# DAC_ADC_External.net
KiCad netlist of a schematic drawn in Altium Designer
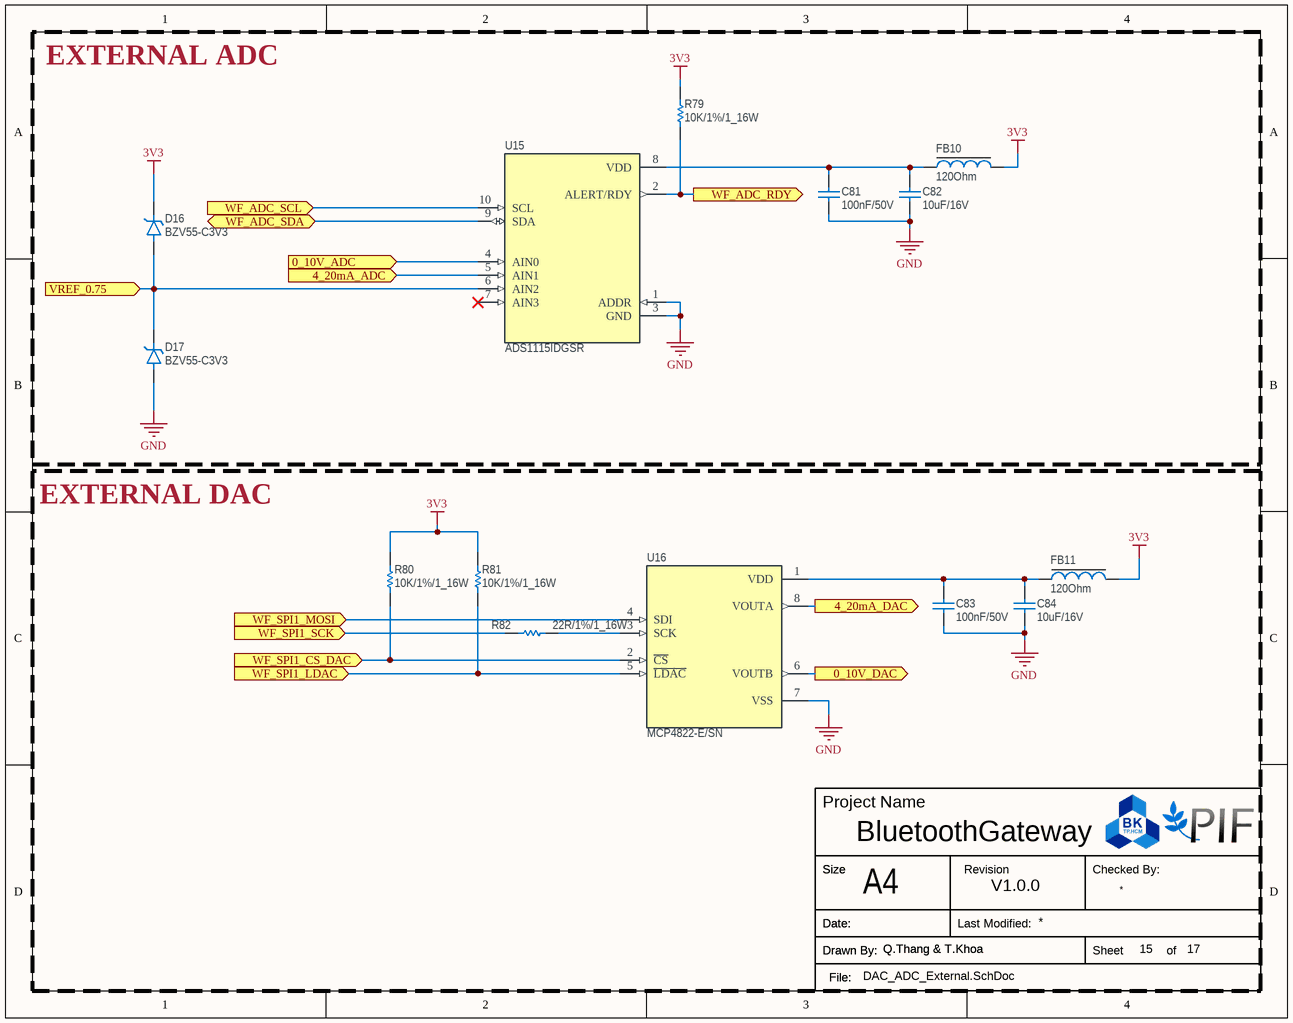
[diagram p0: DAC_ADC_External.SchDoc]

(export (version "E")
  (design (tool "Eeschema 10.0.6"))
  (components
    (comp (ref "C81")
      (value "100nF/50V")
      (footprint "CAP_0603")
      (description "CAP, size 0603, 100nF, 50V")
      (fields (field (name "SUPPLY PART NUMBER") "Tụ Gốm 0603 100nF (0.1uF) 50V"))
      (libsource (lib "BluetoothTracking") (part "Ceramic_Cap_100nF_50V_0603"))
    )
    (comp (ref "C82")
      (value "10uF/16V")
      (footprint "CAP_0603")
      (description "CAP, size 0603, 10uF, 16V")
      (fields (field (name "SUPPLY PART NUMBER") "Tụ Gốm 0603 10uF 16V"))
      (libsource (lib "BluetoothTracking") (part "Ceramic_Cap_10uF_16V_0603"))
    )
    (comp (ref "C83")
      (value "100nF/50V")
      (footprint "CAP_0603")
      (description "CAP, size 0603, 100nF, 50V")
      (fields (field (name "SUPPLY PART NUMBER") "Tụ Gốm 0603 100nF (0.1uF) 50V"))
      (libsource (lib "BluetoothTracking") (part "Ceramic_Cap_100nF_50V_0603"))
    )
    (comp (ref "C84")
      (value "10uF/16V")
      (footprint "CAP_0603")
      (description "CAP, size 0603, 10uF, 16V")
      (fields (field (name "SUPPLY PART NUMBER") "Tụ Gốm 0603 10uF 16V"))
      (libsource (lib "BluetoothTracking") (part "Ceramic_Cap_10uF_16V_0603"))
    )
    (comp (ref "D16")
      (value "BZV55-C3V3")
      (footprint "SOD-80")
      (description "DIODE ZENER 3.3V 500 mW")
      (libsource (lib "BluetoothTracking") (part "Diode_BZV55C3V3"))
    )
    (comp (ref "D17")
      (value "BZV55-C3V3")
      (footprint "SOD-80")
      (description "DIODE ZENER 3.3V 500 mW")
      (libsource (lib "BluetoothTracking") (part "Diode_BZV55C3V3"))
    )
    (comp (ref "FB10")
      (value "120Ohm")
      (footprint "Ferrite_Bead_0805")
      (description "Ferrite Bead, size 0805, 120Ohm, 2A")
      (fields (field (name "SUPPLY PART NUMBER") "CBW201209U121T Ferrite Beads 2A 120 Ohm 0805"))
      (libsource (lib "BluetoothTracking") (part "Ferrite_Bead_120Ohm_2A_0805"))
    )
    (comp (ref "FB11")
      (value "120Ohm")
      (footprint "Ferrite_Bead_0805")
      (description "Ferrite Bead, size 0805, 120Ohm, 2A")
      (fields (field (name "SUPPLY PART NUMBER") "CBW201209U121T Ferrite Beads 2A 120 Ohm 0805"))
      (libsource (lib "BluetoothTracking") (part "Ferrite_Bead_120Ohm_2A_0805"))
    )
    (comp (ref "R79")
      (value "10K/1%/1_16W")
      (footprint "RESISTOR_0402")
      (description "Resistor 0402 10KOhm 1% 1_16W")
      (fields (field (name "SUPPLY PART NUMBER") "Điện Trở 10 KOhm 0402 1%"))
      (libsource (lib "BluetoothTracking") (part "Res_10K_0402_1%"))
    )
    (comp (ref "R80")
      (value "10K/1%/1_16W")
      (footprint "RESISTOR_0402")
      (description "Resistor 0402 10KOhm 1% 1_16W")
      (fields (field (name "SUPPLY PART NUMBER") "Điện Trở 10 KOhm 0402 1%"))
      (libsource (lib "BluetoothTracking") (part "Res_10K_0402_1%"))
    )
    (comp (ref "R81")
      (value "10K/1%/1_16W")
      (footprint "RESISTOR_0402")
      (description "Resistor 0402 10KOhm 1% 1_16W")
      (fields (field (name "SUPPLY PART NUMBER") "Điện Trở 10 KOhm 0402 1%"))
      (libsource (lib "BluetoothTracking") (part "Res_10K_0402_1%"))
    )
    (comp (ref "R82")
      (value "22R/1%/1_16W")
      (footprint "RESISTOR_0402")
      (description "Resistor 0402 22 Ohm 1% 1_16W")
      (libsource (lib "BluetoothTracking") (part "Res_22R_0402_1%"))
    )
    (comp (ref "U15")
      (value "ADS1115IDGSR")
      (footprint "VSSOP-10")
      (fields (field (name "SUPPLY PART NUMBER") "ADS1115IDGSR IC ADC 16-Bit Sigma-Delta 10-VSSOP"))
      (libsource (lib "BluetoothTracking") (part "ADS1115IDGSR"))
    )
    (comp (ref "U16")
      (value "MCP4822-E/SN")
      (footprint "SOIC-8")
      (description "12 Bit Digital to Analog Converter 2 8-SOIC")
      (fields (field (name "SUPPLY PART NUMBER") "MCP4822-E/SN SOIC-8 DAC 12Bit Chính Hãng Microchip"))
      (libsource (lib "BluetoothTracking") (part "MCP4822-E/SN"))
    )
  )
  (nets
    (net (code "1") (name "/0_10V_ADC") (class "Default")
      (node (ref "U15") (pin "4") (pinfunction "AIN0_4") (pintype "input"))
    )
    (net (code "2") (name "/0_10V_DAC") (class "Default")
      (node (ref "U16") (pin "6") (pinfunction "VOUTB_6") (pintype "output"))
    )
    (net (code "3") (name "/4_20mA_ADC") (class "Default")
      (node (ref "U15") (pin "5") (pinfunction "AIN1_5") (pintype "input"))
    )
    (net (code "4") (name "/4_20mA_DAC") (class "Default")
      (node (ref "U16") (pin "8") (pinfunction "VOUTA_8") (pintype "output"))
    )
    (net (code "5") (name "/VREF_0.75") (class "Default")
      (node (ref "D16") (pin "A") (pinfunction "A_A") (pintype "passive"))
      (node (ref "D17") (pin "C") (pinfunction "C_C") (pintype "passive"))
      (node (ref "U15") (pin "6") (pinfunction "AIN2_6") (pintype "input"))
    )
    (net (code "6") (name "/WF_ADC_RDY") (class "Default")
      (node (ref "R79") (pin "1") (pinfunction "1_1") (pintype "passive"))
      (node (ref "U15") (pin "2") (pinfunction "ALERT/RDY_2") (pintype "output"))
    )
    (net (code "7") (name "/WF_ADC_SCL") (class "Default")
      (node (ref "U15") (pin "10") (pinfunction "SCL_10") (pintype "input"))
    )
    (net (code "8") (name "/WF_ADC_SDA") (class "Default")
      (node (ref "U15") (pin "9") (pinfunction "SDA_9") (pintype "bidirectional"))
    )
    (net (code "9") (name "/WF_SPI1_CS_DAC") (class "Default")
      (node (ref "R80") (pin "1") (pinfunction "1_1") (pintype "passive"))
      (node (ref "U16") (pin "2") (pinfunction "~{CS}_2") (pintype "input"))
    )
    (net (code "10") (name "/WF_SPI1_LDAC") (class "Default")
      (node (ref "R81") (pin "1") (pinfunction "1_1") (pintype "passive"))
      (node (ref "U16") (pin "5") (pinfunction "~{LDAC}_5") (pintype "input"))
    )
    (net (code "11") (name "/WF_SPI1_MOSI") (class "Default")
      (node (ref "U16") (pin "4") (pinfunction "SDI_4") (pintype "input"))
    )
    (net (code "12") (name "/WF_SPI1_SCK") (class "Default")
      (node (ref "R82") (pin "1") (pinfunction "1_1") (pintype "passive"))
    )
    (net (code "13") (name "3V3") (class "Default")
      (node (ref "D16") (pin "C") (pinfunction "C_C") (pintype "passive"))
      (node (ref "FB10") (pin "2") (pinfunction "2_2") (pintype "passive"))
      (node (ref "FB11") (pin "2") (pinfunction "2_2") (pintype "passive"))
      (node (ref "R79") (pin "2") (pinfunction "2_2") (pintype "passive"))
      (node (ref "R80") (pin "2") (pinfunction "2_2") (pintype "passive"))
      (node (ref "R81") (pin "2") (pinfunction "2_2") (pintype "passive"))
    )
    (net (code "14") (name "GND") (class "Default")
      (node (ref "C81") (pin "1") (pinfunction "1_1") (pintype "passive"))
      (node (ref "C82") (pin "1") (pinfunction "1_1") (pintype "passive"))
      (node (ref "C83") (pin "1") (pinfunction "1_1") (pintype "passive"))
      (node (ref "C84") (pin "1") (pinfunction "1_1") (pintype "passive"))
      (node (ref "D17") (pin "A") (pinfunction "A_A") (pintype "passive"))
      (node (ref "U15") (pin "1") (pinfunction "ADDR_1") (pintype "input"))
      (node (ref "U15") (pin "3") (pinfunction "GND_3") (pintype "power_in"))
      (node (ref "U16") (pin "7") (pinfunction "VSS_7") (pintype "power_in"))
    )
    (net (code "15") (name "Net-(U15-VDD)") (class "Default")
      (node (ref "C81") (pin "2") (pinfunction "2_2") (pintype "passive"))
      (node (ref "C82") (pin "2") (pinfunction "2_2") (pintype "passive"))
      (node (ref "FB10") (pin "1") (pinfunction "1_1") (pintype "passive"))
      (node (ref "U15") (pin "8") (pinfunction "VDD_8") (pintype "power_in"))
    )
    (net (code "16") (name "Net-(U16-SCK)") (class "Default")
      (node (ref "R82") (pin "2") (pinfunction "2_2") (pintype "passive"))
      (node (ref "U16") (pin "3") (pinfunction "SCK_3") (pintype "input"))
    )
    (net (code "17") (name "Net-(U16-VDD)") (class "Default")
      (node (ref "C83") (pin "2") (pinfunction "2_2") (pintype "passive"))
      (node (ref "C84") (pin "2") (pinfunction "2_2") (pintype "passive"))
      (node (ref "FB11") (pin "1") (pinfunction "1_1") (pintype "passive"))
      (node (ref "U16") (pin "1") (pinfunction "VDD_1") (pintype "power_in"))
    )
    (net (code "18") (name "unconnected-(U15-AIN3-Pad7)") (class "Default")
      (node (ref "U15") (pin "7") (pinfunction "AIN3_7") (pintype "input+no_connect"))
    )
  )
)
